# LCD_TFT.net
KiCad netlist of a schematic drawn in Altium Designer
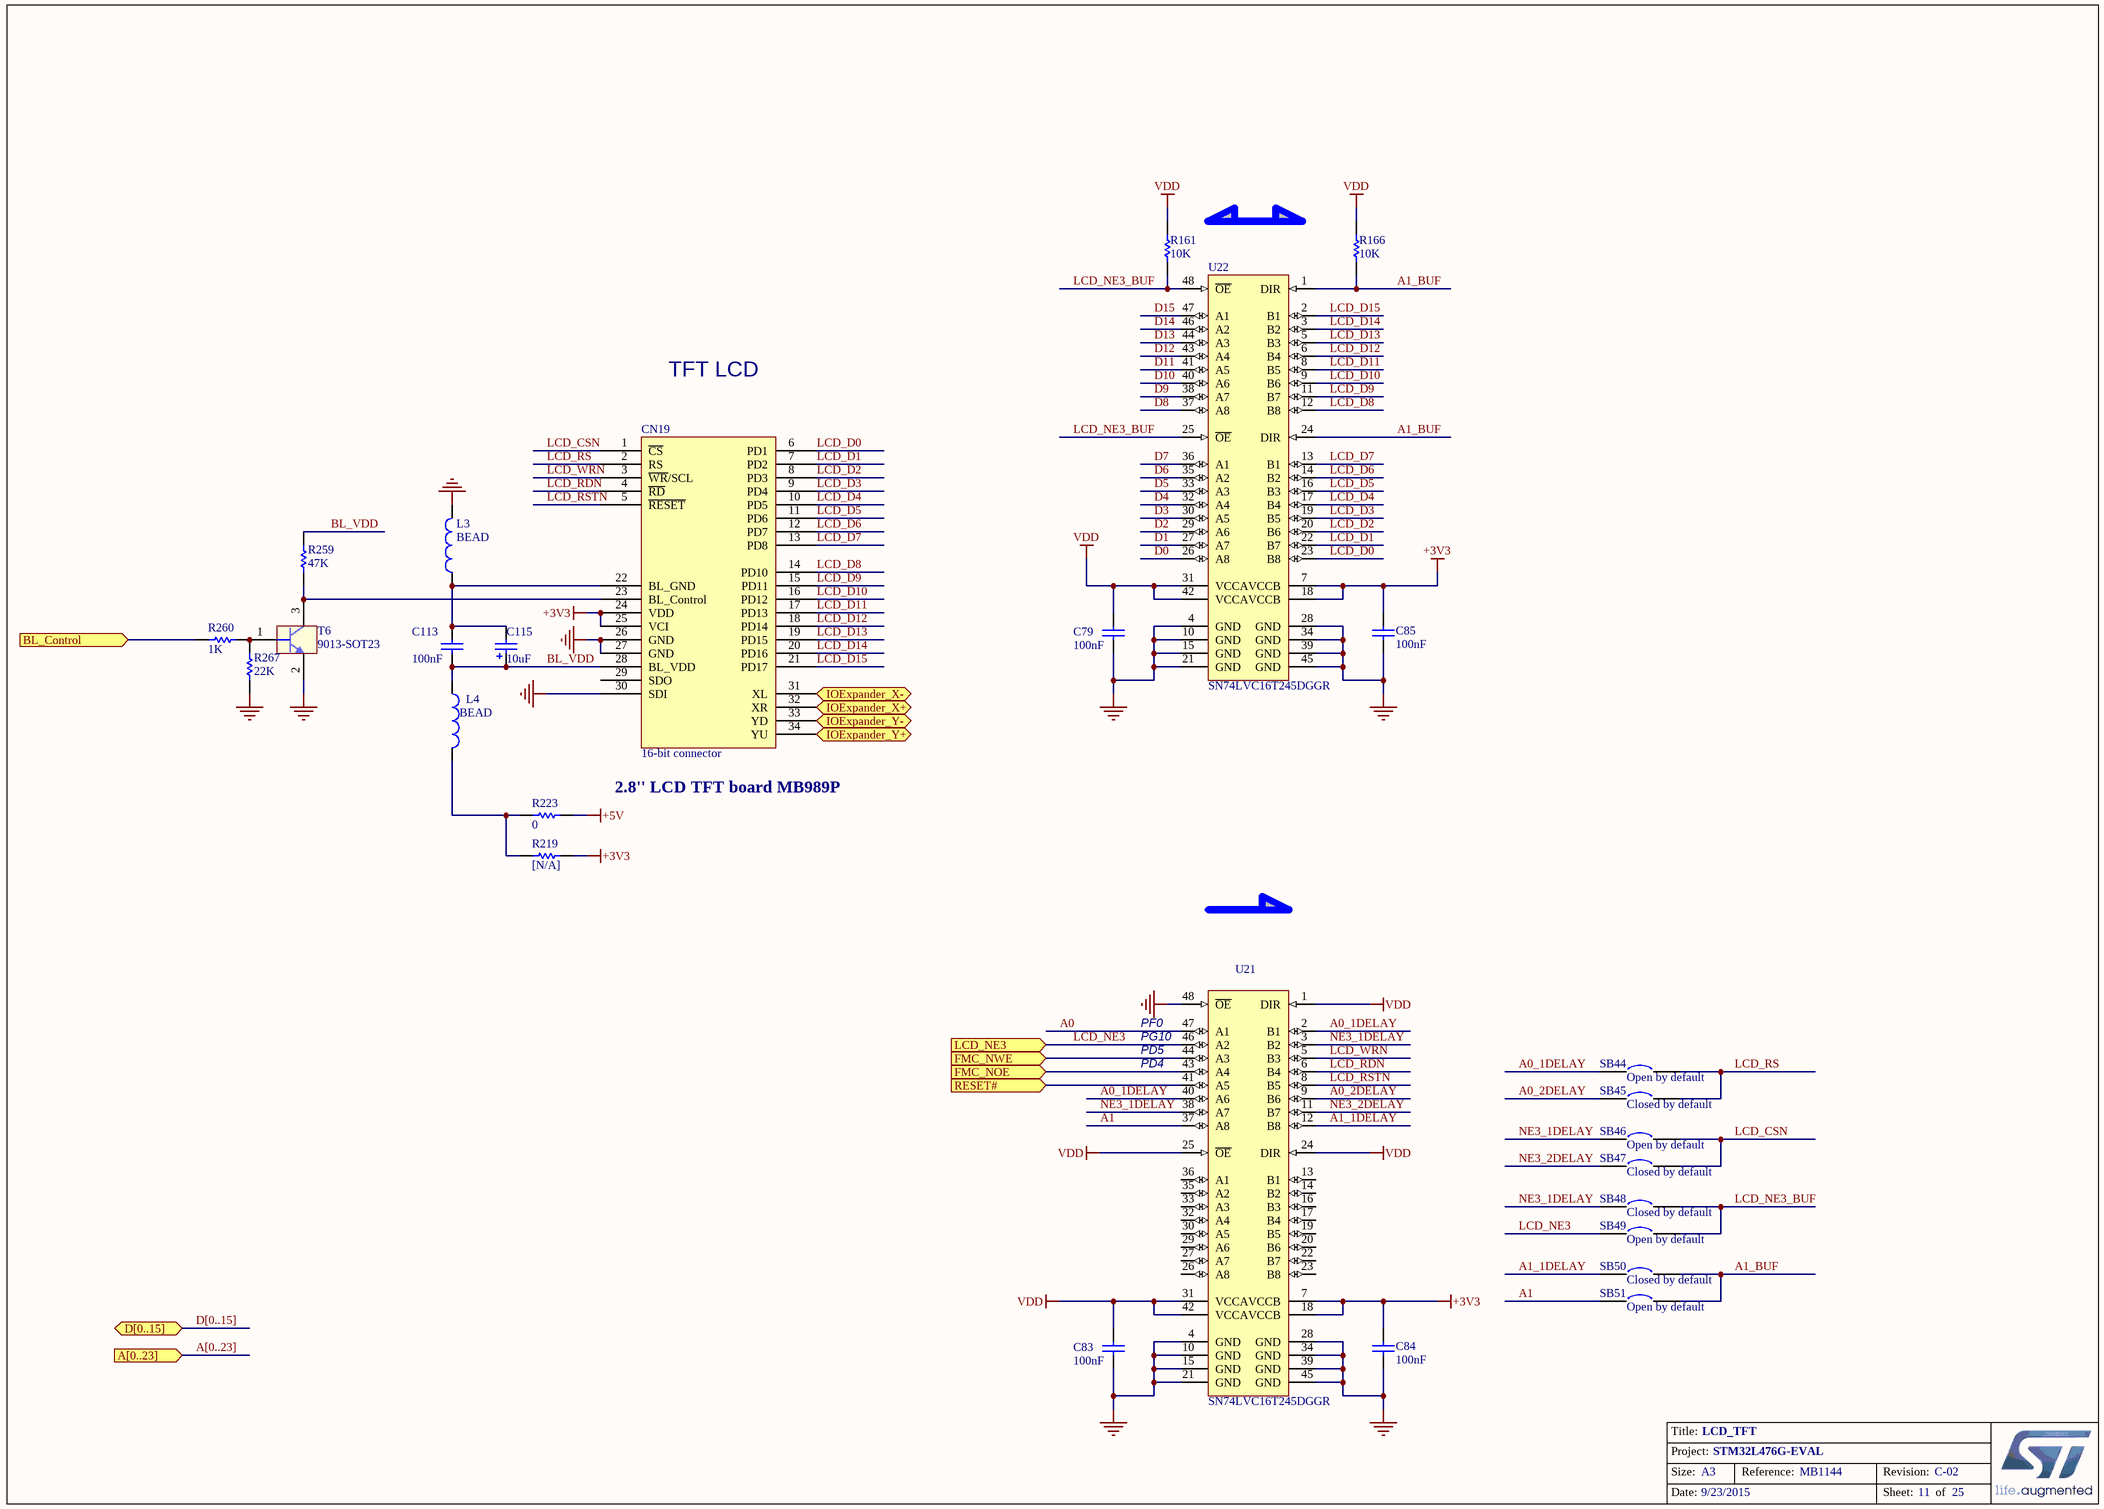
[diagram p0: LCD_TFT.SchDoc]

(export (version "E")
  (design (tool "Eeschema 10.0.6"))
  (components
    (comp (ref "C79")
      (value "100nF")
      (footprint "0402C")
      (description "Capacitor")
      (fields (field (name "PUBLISHER") "Altium Limited"))
      (libsource (lib "Miscellaneous Devices") (part "CAP"))
    )
    (comp (ref "C83")
      (value "100nF")
      (footprint "0402C")
      (description "Capacitor")
      (fields (field (name "PUBLISHER") "Altium Limited"))
      (libsource (lib "Miscellaneous Devices") (part "CAP"))
    )
    (comp (ref "C84")
      (value "100nF")
      (footprint "0402C")
      (description "Capacitor")
      (fields (field (name "PUBLISHER") "Altium Limited"))
      (libsource (lib "Miscellaneous Devices") (part "CAP"))
    )
    (comp (ref "C85")
      (value "100nF")
      (footprint "0402C")
      (description "Capacitor")
      (fields (field (name "PUBLISHER") "Altium Limited"))
      (libsource (lib "Miscellaneous Devices") (part "CAP"))
    )
    (comp (ref "C113")
      (value "100nF")
      (footprint "0402C")
      (description "Capacitor")
      (fields (field (name "PUBLISHER") "Altium Limited"))
      (libsource (lib "Miscellaneous Devices") (part "Cap"))
    )
    (comp (ref "C115")
      (value "10uF")
      (footprint "TAN-A")
      (description "Polarized Capacitor (Radial)")
      (fields (field (name "PUBLISHER") "Altium Limited"))
      (libsource (lib "Miscellaneous Devices") (part "Cap Pol1"))
    )
    (comp (ref "CN19")
      (value "16-bit connector")
      (footprint "HDR_2X17_2R54")
      (description "Female connector 2x17")
      (libsource (lib "MB895") (part "ColorLCD_module_16bits"))
    )
    (comp (ref "L3")
      (value "BEAD")
      (footprint "0603L")
      (description "Inductor")
      (fields (field (name "PUBLISHER") "Altium Limited"))
      (libsource (lib "Miscellaneous Devices") (part "Inductor"))
    )
    (comp (ref "L4")
      (value "BEAD")
      (footprint "0603L")
      (description "Inductor")
      (fields (field (name "PUBLISHER") "Altium Limited"))
      (libsource (lib "Miscellaneous Devices") (part "Inductor"))
    )
    (comp (ref "R161")
      (value "10K")
      (footprint "0402R")
      (description "Resistor")
      (fields (field (name "PUBLISHER") "Altium Limited"))
      (libsource (lib "Miscellaneous Devices") (part "res1"))
    )
    (comp (ref "R166")
      (value "10K")
      (footprint "0402R")
      (description "Resistor")
      (fields (field (name "PUBLISHER") "Altium Limited"))
      (libsource (lib "Miscellaneous Devices") (part "res1"))
    )
    (comp (ref "R219")
      (value "[N/A]")
      (footprint "0603R")
      (description "Resistor")
      (fields (field (name "PUBLISHER") "Altium Limited"))
      (libsource (lib "Miscellaneous Devices") (part "Res1"))
    )
    (comp (ref "R223")
      (value "0")
      (footprint "0603R")
      (description "Resistor")
      (fields (field (name "PUBLISHER") "Altium Limited"))
      (libsource (lib "Miscellaneous Devices") (part "Res1"))
    )
    (comp (ref "R259")
      (value "47K")
      (footprint "0402R")
      (description "Resistor")
      (fields (field (name "PUBLISHER") "Altium Limited"))
      (libsource (lib "Miscellaneous Devices") (part "Res1"))
    )
    (comp (ref "R260")
      (value "1K")
      (footprint "0402R")
      (description "Resistor")
      (fields (field (name "PUBLISHER") "Altium Limited"))
      (libsource (lib "Miscellaneous Devices") (part "Res1"))
    )
    (comp (ref "R267")
      (value "22K")
      (footprint "0402R")
      (description "Resistor")
      (fields (field (name "PUBLISHER") "Altium Limited"))
      (libsource (lib "Miscellaneous Devices") (part "res1"))
    )
    (comp (ref "SB44")
      (value "Open by default")
      (footprint "SB_0603")
      (description "Circuit Breaker")
      (fields (field (name "PUBLISHER") "Altium Limited"))
      (libsource (lib "Miscellaneous Devices") (part "Circuit Breaker"))
    )
    (comp (ref "SB45")
      (value "Closed by default")
      (footprint "SB_0603")
      (description "Circuit Breaker")
      (fields (field (name "PUBLISHER") "Altium Limited"))
      (libsource (lib "Miscellaneous Devices") (part "Circuit Breaker"))
    )
    (comp (ref "SB46")
      (value "Open by default")
      (footprint "SB_0603")
      (description "Circuit Breaker")
      (fields (field (name "PUBLISHER") "Altium Limited"))
      (libsource (lib "Miscellaneous Devices") (part "Circuit Breaker"))
    )
    (comp (ref "SB47")
      (value "Closed by default")
      (footprint "SB_0603")
      (description "Circuit Breaker")
      (fields (field (name "PUBLISHER") "Altium Limited"))
      (libsource (lib "Miscellaneous Devices") (part "Circuit Breaker"))
    )
    (comp (ref "SB48")
      (value "Closed by default")
      (footprint "SB_0603")
      (description "Circuit Breaker")
      (fields (field (name "PUBLISHER") "Altium Limited"))
      (libsource (lib "Miscellaneous Devices") (part "Circuit Breaker"))
    )
    (comp (ref "SB49")
      (value "Open by default")
      (footprint "SB_0603")
      (description "Circuit Breaker")
      (fields (field (name "PUBLISHER") "Altium Limited"))
      (libsource (lib "Miscellaneous Devices") (part "Circuit Breaker"))
    )
    (comp (ref "SB50")
      (value "Closed by default")
      (footprint "SB_0603")
      (description "Circuit Breaker")
      (fields (field (name "PUBLISHER") "Altium Limited"))
      (libsource (lib "Miscellaneous Devices") (part "Circuit Breaker"))
    )
    (comp (ref "SB51")
      (value "Open by default")
      (footprint "SB_0603")
      (description "Circuit Breaker")
      (fields (field (name "PUBLISHER") "Altium Limited"))
      (libsource (lib "Miscellaneous Devices") (part "Circuit Breaker"))
    )
    (comp (ref "T6")
      (value "9013-SOT23")
      (footprint "SOT-23")
      (description "NPN Bipolar Transistor, SOT-23 Footprint")
      (libsource (lib "MCD_TOOLS") (part "9013-SOT23"))
    )
    (comp (ref "U21")
      (value "SN74LVC16T245DGGR")
      (footprint "TSSOP48_0R5_12R5X8R1")
      (libsource (lib "MB964_1") (part "SN74LVC16T245"))
    )
    (comp (ref "U22")
      (value "SN74LVC16T245DGGR")
      (footprint "TSSOP48_0R5_12R5X8R1")
      (libsource (lib "MB964_1") (part "SN74LVC16T245"))
    )
  )
  (nets
    (net (code "23") (name "+3V3") (class "Default")
      (node (ref "C84") (pin "1") (pinfunction "1_1") (pintype "passive"))
      (node (ref "C85") (pin "1") (pinfunction "1_1") (pintype "passive"))
      (node (ref "CN19") (pin "24") (pinfunction "VDD_24") (pintype "passive"))
      (node (ref "CN19") (pin "25") (pinfunction "VCI_25") (pintype "passive"))
      (node (ref "R219") (pin "1") (pinfunction "1_1") (pintype "passive"))
      (node (ref "U21") (pin "18") (pinfunction "VCCB_18") (pintype "power_in"))
      (node (ref "U21") (pin "7") (pinfunction "VCCB_7") (pintype "power_in"))
      (node (ref "U22") (pin "18") (pinfunction "VCCB_18") (pintype "power_in"))
      (node (ref "U22") (pin "7") (pinfunction "VCCB_7") (pintype "power_in"))
    )
    (net (code "24") (name "+5V") (class "Default")
      (node (ref "R223") (pin "1") (pinfunction "1_1") (pintype "passive"))
    )
    (net (code "25") (name "/A0") (class "Default")
      (node (ref "U21") (pin "47") (pinfunction "A1_47") (pintype "bidirectional"))
    )
    (net (code "26") (name "/A0_1DELAY") (class "Default")
      (node (ref "SB44") (pin "1") (pinfunction "1_1") (pintype "passive"))
      (node (ref "U21") (pin "2") (pinfunction "B1_2") (pintype "bidirectional"))
      (node (ref "U21") (pin "40") (pinfunction "A6_40") (pintype "bidirectional"))
    )
    (net (code "27") (name "/A0_2DELAY") (class "Default")
      (node (ref "SB45") (pin "1") (pinfunction "1_1") (pintype "passive"))
      (node (ref "U21") (pin "9") (pinfunction "B6_9") (pintype "bidirectional"))
    )
    (net (code "28") (name "/A1") (class "Default")
      (node (ref "SB51") (pin "1") (pinfunction "1_1") (pintype "passive"))
      (node (ref "U21") (pin "37") (pinfunction "A8_37") (pintype "bidirectional"))
    )
    (net (code "29") (name "/A1_1DELAY") (class "Default")
      (node (ref "SB50") (pin "1") (pinfunction "1_1") (pintype "passive"))
      (node (ref "U21") (pin "12") (pinfunction "B8_12") (pintype "bidirectional"))
    )
    (net (code "30") (name "/A1_BUF") (class "Default")
      (node (ref "R166") (pin "2") (pinfunction "2_2") (pintype "passive"))
      (node (ref "SB50") (pin "2") (pinfunction "2_2") (pintype "passive"))
      (node (ref "SB51") (pin "2") (pinfunction "2_2") (pintype "passive"))
      (node (ref "U22") (pin "1") (pinfunction "DIR_1") (pintype "input"))
      (node (ref "U22") (pin "24") (pinfunction "DIR_24") (pintype "input"))
    )
    (net (code "32") (name "/BL_Control") (class "Default")
      (node (ref "R260") (pin "1") (pinfunction "1_1") (pintype "passive"))
    )
    (net (code "33") (name "/BL_VDD") (class "Default")
      (node (ref "C113") (pin "2") (pinfunction "2_2") (pintype "passive"))
      (node (ref "C115") (pin "1") (pinfunction "1_1") (pintype "passive"))
      (node (ref "CN19") (pin "28") (pinfunction "BL_VDD_28") (pintype "passive"))
      (node (ref "L4") (pin "1") (pinfunction "1_1") (pintype "passive"))
      (node (ref "R259") (pin "1") (pinfunction "1_1") (pintype "passive"))
    )
    (net (code "34") (name "/D0") (class "Default")
      (node (ref "U22") (pin "26") (pinfunction "A8_26") (pintype "bidirectional"))
    )
    (net (code "35") (name "/D1") (class "Default")
      (node (ref "U22") (pin "27") (pinfunction "A7_27") (pintype "bidirectional"))
    )
    (net (code "36") (name "/D2") (class "Default")
      (node (ref "U22") (pin "29") (pinfunction "A6_29") (pintype "bidirectional"))
    )
    (net (code "37") (name "/D3") (class "Default")
      (node (ref "U22") (pin "30") (pinfunction "A5_30") (pintype "bidirectional"))
    )
    (net (code "38") (name "/D4") (class "Default")
      (node (ref "U22") (pin "32") (pinfunction "A4_32") (pintype "bidirectional"))
    )
    (net (code "39") (name "/D5") (class "Default")
      (node (ref "U22") (pin "33") (pinfunction "A3_33") (pintype "bidirectional"))
    )
    (net (code "40") (name "/D6") (class "Default")
      (node (ref "U22") (pin "35") (pinfunction "A2_35") (pintype "bidirectional"))
    )
    (net (code "41") (name "/D7") (class "Default")
      (node (ref "U22") (pin "36") (pinfunction "A1_36") (pintype "bidirectional"))
    )
    (net (code "42") (name "/D8") (class "Default")
      (node (ref "U22") (pin "37") (pinfunction "A8_37") (pintype "bidirectional"))
    )
    (net (code "43") (name "/D9") (class "Default")
      (node (ref "U22") (pin "38") (pinfunction "A7_38") (pintype "bidirectional"))
    )
    (net (code "44") (name "/D10") (class "Default")
      (node (ref "U22") (pin "40") (pinfunction "A6_40") (pintype "bidirectional"))
    )
    (net (code "45") (name "/D11") (class "Default")
      (node (ref "U22") (pin "41") (pinfunction "A5_41") (pintype "bidirectional"))
    )
    (net (code "46") (name "/D12") (class "Default")
      (node (ref "U22") (pin "43") (pinfunction "A4_43") (pintype "bidirectional"))
    )
    (net (code "47") (name "/D13") (class "Default")
      (node (ref "U22") (pin "44") (pinfunction "A3_44") (pintype "bidirectional"))
    )
    (net (code "48") (name "/D14") (class "Default")
      (node (ref "U22") (pin "46") (pinfunction "A2_46") (pintype "bidirectional"))
    )
    (net (code "49") (name "/D15") (class "Default")
      (node (ref "U22") (pin "47") (pinfunction "A1_47") (pintype "bidirectional"))
    )
    (net (code "51") (name "/FMC_NOE") (class "Default")
      (node (ref "U21") (pin "43") (pinfunction "A4_43") (pintype "bidirectional"))
    )
    (net (code "52") (name "/FMC_NWE") (class "Default")
      (node (ref "U21") (pin "44") (pinfunction "A3_44") (pintype "bidirectional"))
    )
    (net (code "53") (name "/IOExpander_X+") (class "Default")
      (node (ref "CN19") (pin "32") (pinfunction "XR_32") (pintype "passive"))
    )
    (net (code "54") (name "/IOExpander_X-") (class "Default")
      (node (ref "CN19") (pin "31") (pinfunction "XL_31") (pintype "passive"))
    )
    (net (code "55") (name "/IOExpander_Y+") (class "Default")
      (node (ref "CN19") (pin "34") (pinfunction "YU_34") (pintype "passive"))
    )
    (net (code "56") (name "/IOExpander_Y-") (class "Default")
      (node (ref "CN19") (pin "33") (pinfunction "YD_33") (pintype "passive"))
    )
    (net (code "57") (name "/LCD_CSN") (class "Default")
      (node (ref "CN19") (pin "1") (pinfunction "~{CS}_1") (pintype "passive"))
      (node (ref "SB46") (pin "2") (pinfunction "2_2") (pintype "passive"))
      (node (ref "SB47") (pin "2") (pinfunction "2_2") (pintype "passive"))
    )
    (net (code "58") (name "/LCD_D0") (class "Default")
      (node (ref "CN19") (pin "6") (pinfunction "PD1_6") (pintype "passive"))
      (node (ref "U22") (pin "23") (pinfunction "B8_23") (pintype "bidirectional"))
    )
    (net (code "59") (name "/LCD_D1") (class "Default")
      (node (ref "CN19") (pin "7") (pinfunction "PD2_7") (pintype "passive"))
      (node (ref "U22") (pin "22") (pinfunction "B7_22") (pintype "bidirectional"))
    )
    (net (code "60") (name "/LCD_D2") (class "Default")
      (node (ref "CN19") (pin "8") (pinfunction "PD3_8") (pintype "passive"))
      (node (ref "U22") (pin "20") (pinfunction "B6_20") (pintype "bidirectional"))
    )
    (net (code "61") (name "/LCD_D3") (class "Default")
      (node (ref "CN19") (pin "9") (pinfunction "PD4_9") (pintype "passive"))
      (node (ref "U22") (pin "19") (pinfunction "B5_19") (pintype "bidirectional"))
    )
    (net (code "62") (name "/LCD_D4") (class "Default")
      (node (ref "CN19") (pin "10") (pinfunction "PD5_10") (pintype "passive"))
      (node (ref "U22") (pin "17") (pinfunction "B4_17") (pintype "bidirectional"))
    )
    (net (code "63") (name "/LCD_D5") (class "Default")
      (node (ref "CN19") (pin "11") (pinfunction "PD6_11") (pintype "passive"))
      (node (ref "U22") (pin "16") (pinfunction "B3_16") (pintype "bidirectional"))
    )
    (net (code "64") (name "/LCD_D6") (class "Default")
      (node (ref "CN19") (pin "12") (pinfunction "PD7_12") (pintype "passive"))
      (node (ref "U22") (pin "14") (pinfunction "B2_14") (pintype "bidirectional"))
    )
    (net (code "65") (name "/LCD_D7") (class "Default")
      (node (ref "CN19") (pin "13") (pinfunction "PD8_13") (pintype "passive"))
      (node (ref "U22") (pin "13") (pinfunction "B1_13") (pintype "bidirectional"))
    )
    (net (code "66") (name "/LCD_D8") (class "Default")
      (node (ref "CN19") (pin "14") (pinfunction "PD10_14") (pintype "passive"))
      (node (ref "U22") (pin "12") (pinfunction "B8_12") (pintype "bidirectional"))
    )
    (net (code "67") (name "/LCD_D9") (class "Default")
      (node (ref "CN19") (pin "15") (pinfunction "PD11_15") (pintype "passive"))
      (node (ref "U22") (pin "11") (pinfunction "B7_11") (pintype "bidirectional"))
    )
    (net (code "68") (name "/LCD_D10") (class "Default")
      (node (ref "CN19") (pin "16") (pinfunction "PD12_16") (pintype "passive"))
      (node (ref "U22") (pin "9") (pinfunction "B6_9") (pintype "bidirectional"))
    )
    (net (code "69") (name "/LCD_D11") (class "Default")
      (node (ref "CN19") (pin "17") (pinfunction "PD13_17") (pintype "passive"))
      (node (ref "U22") (pin "8") (pinfunction "B5_8") (pintype "bidirectional"))
    )
    (net (code "70") (name "/LCD_D12") (class "Default")
      (node (ref "CN19") (pin "18") (pinfunction "PD14_18") (pintype "passive"))
      (node (ref "U22") (pin "6") (pinfunction "B4_6") (pintype "bidirectional"))
    )
    (net (code "71") (name "/LCD_D13") (class "Default")
      (node (ref "CN19") (pin "19") (pinfunction "PD15_19") (pintype "passive"))
      (node (ref "U22") (pin "5") (pinfunction "B3_5") (pintype "bidirectional"))
    )
    (net (code "72") (name "/LCD_D14") (class "Default")
      (node (ref "CN19") (pin "20") (pinfunction "PD16_20") (pintype "passive"))
      (node (ref "U22") (pin "3") (pinfunction "B2_3") (pintype "bidirectional"))
    )
    (net (code "73") (name "/LCD_D15") (class "Default")
      (node (ref "CN19") (pin "21") (pinfunction "PD17_21") (pintype "passive"))
      (node (ref "U22") (pin "2") (pinfunction "B1_2") (pintype "bidirectional"))
    )
    (net (code "74") (name "/LCD_NE3") (class "Default")
      (node (ref "SB49") (pin "1") (pinfunction "1_1") (pintype "passive"))
      (node (ref "U21") (pin "46") (pinfunction "A2_46") (pintype "bidirectional"))
    )
    (net (code "75") (name "/LCD_NE3_BUF") (class "Default")
      (node (ref "R161") (pin "2") (pinfunction "2_2") (pintype "passive"))
      (node (ref "SB48") (pin "2") (pinfunction "2_2") (pintype "passive"))
      (node (ref "SB49") (pin "2") (pinfunction "2_2") (pintype "passive"))
      (node (ref "U22") (pin "25") (pinfunction "~{OE}_25") (pintype "input"))
      (node (ref "U22") (pin "48") (pinfunction "~{OE}_48") (pintype "input"))
    )
    (net (code "76") (name "/LCD_RDN") (class "Default")
      (node (ref "CN19") (pin "4") (pinfunction "~{RD}_4") (pintype "passive"))
      (node (ref "U21") (pin "6") (pinfunction "B4_6") (pintype "bidirectional"))
    )
    (net (code "77") (name "/LCD_RS") (class "Default")
      (node (ref "CN19") (pin "2") (pinfunction "RS_2") (pintype "passive"))
      (node (ref "SB44") (pin "2") (pinfunction "2_2") (pintype "passive"))
      (node (ref "SB45") (pin "2") (pinfunction "2_2") (pintype "passive"))
    )
    (net (code "78") (name "/LCD_RSTN") (class "Default")
      (node (ref "CN19") (pin "5") (pinfunction "~{RESET}_5") (pintype "passive"))
      (node (ref "U21") (pin "8") (pinfunction "B5_8") (pintype "bidirectional"))
    )
    (net (code "79") (name "/LCD_WRN") (class "Default")
      (node (ref "CN19") (pin "3") (pinfunction "~{WR}/SCL_3") (pintype "passive"))
      (node (ref "U21") (pin "5") (pinfunction "B3_5") (pintype "bidirectional"))
    )
    (net (code "80") (name "/NE3_1DELAY") (class "Default")
      (node (ref "SB46") (pin "1") (pinfunction "1_1") (pintype "passive"))
      (node (ref "SB48") (pin "1") (pinfunction "1_1") (pintype "passive"))
      (node (ref "U21") (pin "3") (pinfunction "B2_3") (pintype "bidirectional"))
      (node (ref "U21") (pin "38") (pinfunction "A7_38") (pintype "bidirectional"))
    )
    (net (code "81") (name "/NE3_2DELAY") (class "Default")
      (node (ref "SB47") (pin "1") (pinfunction "1_1") (pintype "passive"))
      (node (ref "U21") (pin "11") (pinfunction "B7_11") (pintype "bidirectional"))
    )
    (net (code "82") (name "/RESET#") (class "Default")
      (node (ref "U21") (pin "41") (pinfunction "A5_41") (pintype "bidirectional"))
    )
    (net (code "83") (name "GND") (class "Default")
      (node (ref "C79") (pin "2") (pinfunction "2_2") (pintype "passive"))
      (node (ref "C83") (pin "2") (pinfunction "2_2") (pintype "passive"))
      (node (ref "C84") (pin "2") (pinfunction "2_2") (pintype "passive"))
      (node (ref "C85") (pin "2") (pinfunction "2_2") (pintype "passive"))
      (node (ref "CN19") (pin "26") (pinfunction "GND_26") (pintype "passive"))
      (node (ref "CN19") (pin "27") (pinfunction "GND_27") (pintype "passive"))
      (node (ref "CN19") (pin "30") (pinfunction "SDI_30") (pintype "passive"))
      (node (ref "L3") (pin "2") (pinfunction "2_2") (pintype "passive"))
      (node (ref "R267") (pin "2") (pinfunction "2_2") (pintype "passive"))
      (node (ref "T6") (pin "2") (pinfunction "E_2") (pintype "passive"))
      (node (ref "U21") (pin "10") (pinfunction "GND_10") (pintype "power_in"))
      (node (ref "U21") (pin "15") (pinfunction "GND_15") (pintype "power_in"))
      (node (ref "U21") (pin "21") (pinfunction "GND_21") (pintype "power_in"))
      (node (ref "U21") (pin "28") (pinfunction "GND_28") (pintype "power_in"))
      (node (ref "U21") (pin "34") (pinfunction "GND_34") (pintype "power_in"))
      (node (ref "U21") (pin "39") (pinfunction "GND_39") (pintype "power_in"))
      (node (ref "U21") (pin "4") (pinfunction "GND_4") (pintype "power_in"))
      (node (ref "U21") (pin "45") (pinfunction "GND_45") (pintype "power_in"))
      (node (ref "U21") (pin "48") (pinfunction "~{OE}_48") (pintype "input"))
      (node (ref "U22") (pin "10") (pinfunction "GND_10") (pintype "power_in"))
      (node (ref "U22") (pin "15") (pinfunction "GND_15") (pintype "power_in"))
      (node (ref "U22") (pin "21") (pinfunction "GND_21") (pintype "power_in"))
      (node (ref "U22") (pin "28") (pinfunction "GND_28") (pintype "power_in"))
      (node (ref "U22") (pin "34") (pinfunction "GND_34") (pintype "power_in"))
      (node (ref "U22") (pin "39") (pinfunction "GND_39") (pintype "power_in"))
      (node (ref "U22") (pin "4") (pinfunction "GND_4") (pintype "power_in"))
      (node (ref "U22") (pin "45") (pinfunction "GND_45") (pintype "power_in"))
    )
    (net (code "84") (name "Net-(CN19-BL_Control)") (class "Default")
      (node (ref "CN19") (pin "23") (pinfunction "BL_Control_23") (pintype "passive"))
      (node (ref "R259") (pin "2") (pinfunction "2_2") (pintype "passive"))
      (node (ref "T6") (pin "3") (pinfunction "C_3") (pintype "passive"))
    )
    (net (code "85") (name "Net-(CN19-BL_GND)") (class "Default")
      (node (ref "C113") (pin "1") (pinfunction "1_1") (pintype "passive"))
      (node (ref "C115") (pin "2") (pinfunction "2_2") (pintype "passive"))
      (node (ref "CN19") (pin "22") (pinfunction "BL_GND_22") (pintype "passive"))
      (node (ref "L3") (pin "1") (pinfunction "1_1") (pintype "passive"))
    )
    (net (code "86") (name "Net-(L4-Pad2)") (class "Default")
      (node (ref "L4") (pin "2") (pinfunction "2_2") (pintype "passive"))
      (node (ref "R219") (pin "2") (pinfunction "2_2") (pintype "passive"))
      (node (ref "R223") (pin "2") (pinfunction "2_2") (pintype "passive"))
    )
    (net (code "87") (name "Net-(T6-B)") (class "Default")
      (node (ref "R260") (pin "2") (pinfunction "2_2") (pintype "passive"))
      (node (ref "R267") (pin "1") (pinfunction "1_1") (pintype "passive"))
      (node (ref "T6") (pin "1") (pinfunction "B_1") (pintype "passive"))
    )
    (net (code "88") (name "VDD") (class "Default")
      (node (ref "C79") (pin "1") (pinfunction "1_1") (pintype "passive"))
      (node (ref "C83") (pin "1") (pinfunction "1_1") (pintype "passive"))
      (node (ref "R161") (pin "1") (pinfunction "1_1") (pintype "passive"))
      (node (ref "R166") (pin "1") (pinfunction "1_1") (pintype "passive"))
      (node (ref "U21") (pin "1") (pinfunction "DIR_1") (pintype "input"))
      (node (ref "U21") (pin "24") (pinfunction "DIR_24") (pintype "input"))
      (node (ref "U21") (pin "25") (pinfunction "~{OE}_25") (pintype "input"))
      (node (ref "U21") (pin "31") (pinfunction "VCCA_31") (pintype "power_in"))
      (node (ref "U21") (pin "42") (pinfunction "VCCA_42") (pintype "power_in"))
      (node (ref "U22") (pin "31") (pinfunction "VCCA_31") (pintype "power_in"))
      (node (ref "U22") (pin "42") (pinfunction "VCCA_42") (pintype "power_in"))
    )
    (net (code "89") (name "unconnected-(CN19-SDO-Pad29)") (class "Default")
      (node (ref "CN19") (pin "29") (pinfunction "SDO_29") (pintype "passive"))
    )
    (net (code "90") (name "unconnected-(U21-A1-Pad36)") (class "Default")
      (node (ref "U21") (pin "36") (pinfunction "A1_36") (pintype "bidirectional"))
    )
    (net (code "91") (name "unconnected-(U21-A2-Pad35)") (class "Default")
      (node (ref "U21") (pin "35") (pinfunction "A2_35") (pintype "bidirectional"))
    )
    (net (code "92") (name "unconnected-(U21-A3-Pad33)") (class "Default")
      (node (ref "U21") (pin "33") (pinfunction "A3_33") (pintype "bidirectional"))
    )
    (net (code "93") (name "unconnected-(U21-A4-Pad32)") (class "Default")
      (node (ref "U21") (pin "32") (pinfunction "A4_32") (pintype "bidirectional"))
    )
    (net (code "94") (name "unconnected-(U21-A5-Pad30)") (class "Default")
      (node (ref "U21") (pin "30") (pinfunction "A5_30") (pintype "bidirectional"))
    )
    (net (code "95") (name "unconnected-(U21-A6-Pad29)") (class "Default")
      (node (ref "U21") (pin "29") (pinfunction "A6_29") (pintype "bidirectional"))
    )
    (net (code "96") (name "unconnected-(U21-A7-Pad27)") (class "Default")
      (node (ref "U21") (pin "27") (pinfunction "A7_27") (pintype "bidirectional"))
    )
    (net (code "97") (name "unconnected-(U21-A8-Pad26)") (class "Default")
      (node (ref "U21") (pin "26") (pinfunction "A8_26") (pintype "bidirectional"))
    )
    (net (code "98") (name "unconnected-(U21-B1-Pad13)") (class "Default")
      (node (ref "U21") (pin "13") (pinfunction "B1_13") (pintype "bidirectional"))
    )
    (net (code "99") (name "unconnected-(U21-B2-Pad14)") (class "Default")
      (node (ref "U21") (pin "14") (pinfunction "B2_14") (pintype "bidirectional"))
    )
    (net (code "100") (name "unconnected-(U21-B3-Pad16)") (class "Default")
      (node (ref "U21") (pin "16") (pinfunction "B3_16") (pintype "bidirectional"))
    )
    (net (code "101") (name "unconnected-(U21-B4-Pad17)") (class "Default")
      (node (ref "U21") (pin "17") (pinfunction "B4_17") (pintype "bidirectional"))
    )
    (net (code "102") (name "unconnected-(U21-B5-Pad19)") (class "Default")
      (node (ref "U21") (pin "19") (pinfunction "B5_19") (pintype "bidirectional"))
    )
    (net (code "103") (name "unconnected-(U21-B6-Pad20)") (class "Default")
      (node (ref "U21") (pin "20") (pinfunction "B6_20") (pintype "bidirectional"))
    )
    (net (code "104") (name "unconnected-(U21-B7-Pad22)") (class "Default")
      (node (ref "U21") (pin "22") (pinfunction "B7_22") (pintype "bidirectional"))
    )
    (net (code "105") (name "unconnected-(U21-B8-Pad23)") (class "Default")
      (node (ref "U21") (pin "23") (pinfunction "B8_23") (pintype "bidirectional"))
    )
  )
)
